# ProPrj___2025-08-19.net
KiCad netlist of a schematic drawn in EasyEDA Pro
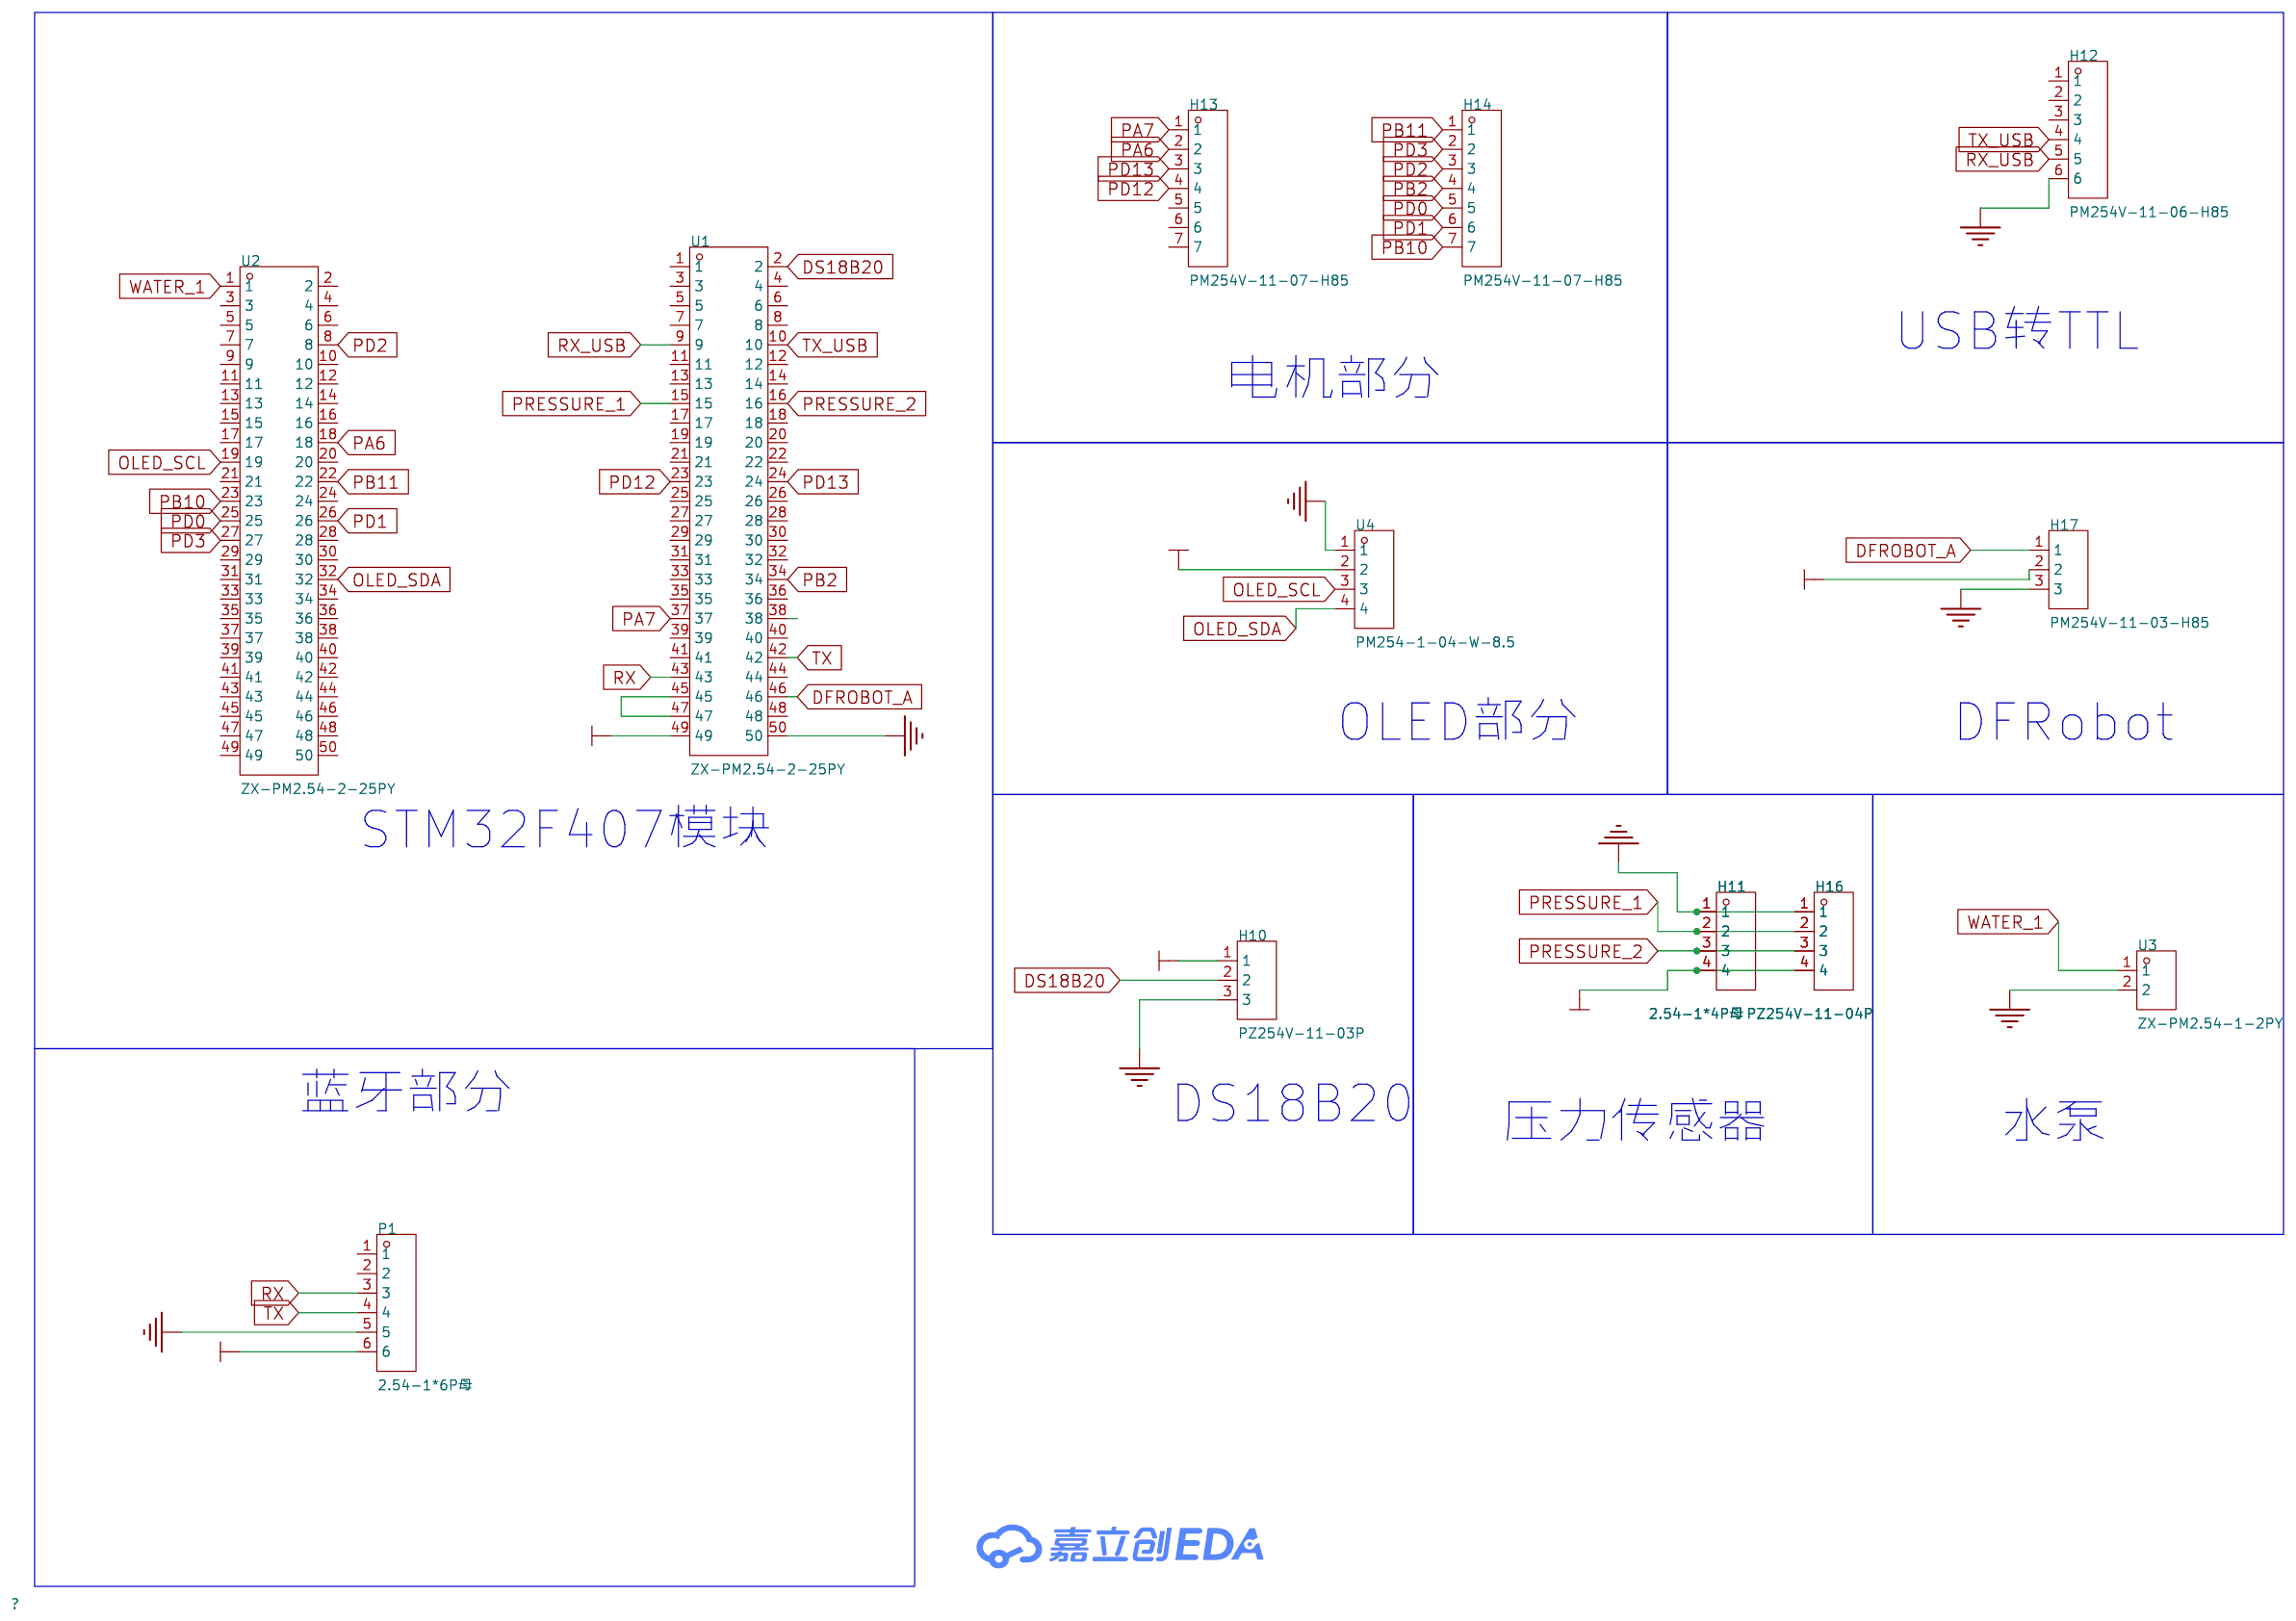
[diagram p0: schematic sheet]

(export (version "E")
  (design (tool "Eeschema 10.0.6"))
  (components
    (comp (ref "H10")
      (value "PZ254V-11-03P")
      (footprint "easyedapro:HDR-TH_3P-P2.54-V-M")
      (fields (field (name "Manufacturer") "XFCN(兴飞)"))
      (libsource (lib "easyedapro") (part "PZ254V-11-03P_C2937625"))
    )
    (comp (ref "H11")
      (value "2.54-1*4P母")
      (footprint "easyedapro:HDR-TH_4P-P2.54-V-F")
      (fields (field (name "Manufacturer") "BOOMELE(博穆精密)"))
      (libsource (lib "easyedapro") (part "2.54-1*4P母"))
    )
    (comp (ref "H12")
      (value "PM254V-11-06-H85")
      (footprint "easyedapro:HDR-TH_6P-P2.54-V-F")
      (fields (field (name "Manufacturer") "XFCN(兴飞)"))
      (libsource (lib "easyedapro") (part "PM254V-11-06-H85"))
    )
    (comp (ref "H13")
      (value "PM254V-11-07-H85")
      (footprint "easyedapro:HDR-TH_7P-P2.54-V-F")
      (fields (field (name "Manufacturer") "XFCN(兴飞)"))
      (libsource (lib "easyedapro") (part "PM254V-11-07-H85"))
    )
    (comp (ref "H14")
      (value "PM254V-11-07-H85")
      (footprint "easyedapro:HDR-TH_7P-P2.54-V-F")
      (fields (field (name "Manufacturer") "XFCN(兴飞)"))
      (libsource (lib "easyedapro") (part "PM254V-11-07-H85"))
    )
    (comp (ref "H16")
      (value "PZ254V-11-04P")
      (footprint "easyedapro:HDR-TH_4P-P2.54-V-M")
      (fields (field (name "Manufacturer") "XFCN(兴飞)"))
      (libsource (lib "easyedapro") (part "PZ254V-11-04P_C2691448"))
    )
    (comp (ref "H17")
      (value "PM254V-11-03-H85")
      (footprint "easyedapro:HDR-TH_3P-P2.54-V-F")
      (description "插孔结构:1x3P;间距:2.54mm;行距:-;安装类型:直插;排数:单排;总孔位数:3P;塑高:-;触头材质:黄铜;触头镀层:-;")
      (fields (field (name "Manufacturer") "XFCN(兴飞)"))
      (libsource (lib "easyedapro") (part "PM254V-11-03-H85"))
    )
    (comp (ref "P1")
      (value "2.54-1*6P母")
      (footprint "easyedapro:HDR-TH_6P-P2.54-V-F")
      (description "插孔结构:1x6P;间距:2.54mm;行距:-;安装类型:直插;排数:单排;总孔位数:6P;塑高:-;触头材质:-;触头镀层:-;")
      (fields (field (name "Manufacturer") "BOOMELE(博穆精密)"))
      (libsource (lib "easyedapro") (part "Header-Female-2.54_1x6"))
    )
    (comp (ref "U1")
      (value "ZX-PM2.54-2-25PY")
      (footprint "easyedapro:HDR-TH_50P-P2.54-V-F-R2-C25-S2.54-1")
      (fields (field (name "Manufacturer") "Megastar(兆星)"))
      (libsource (lib "easyedapro") (part "ZX-PM2.54-2-25PY"))
    )
    (comp (ref "U2")
      (value "ZX-PM2.54-2-25PY")
      (footprint "easyedapro:HDR-TH_50P-P2.54-V-F-R2-C25-S2.54-1")
      (fields (field (name "Manufacturer") "Megastar(兆星)"))
      (libsource (lib "easyedapro") (part "ZX-PM2.54-2-25PY"))
    )
    (comp (ref "U3")
      (value "ZX-PM2.54-1-2PY")
      (footprint "easyedapro:HDR-TH_2P-P2.54-V-F")
      (fields (field (name "Manufacturer") "Megastar(兆星)"))
      (libsource (lib "easyedapro") (part "ZX-PM2.54-1-2PY"))
    )
    (comp (ref "U4")
      (value "PM254-1-04-W-8.5")
      (footprint "easyedapro:HDR-TH_4P-P2.54-H-F-W10.0-N")
      (fields (field (name "Manufacturer") "HCTL(华灿天禄)"))
      (libsource (lib "easyedapro") (part "PM254-1-04-W-8.5"))
    )
  )
  (nets
    (net (code "1") (name "3.3V") (class "Default")
      (node (ref "H10") (pin "1") (pinfunction "1_1") (pintype "unspecified"))
      (node (ref "H11") (pin "4") (pinfunction "4_4") (pintype "unspecified"))
      (node (ref "H16") (pin "4") (pinfunction "4_4") (pintype "unspecified"))
      (node (ref "H17") (pin "2") (pinfunction "2_2") (pintype "unspecified"))
      (node (ref "P1") (pin "6") (pinfunction "6_6") (pintype "unspecified"))
      (node (ref "U1") (pin "49") (pinfunction "49_49") (pintype "unspecified"))
      (node (ref "U4") (pin "2") (pinfunction "2_2") (pintype "unspecified"))
    )
    (net (code "2") (name "DFROBOT_A") (class "Default")
      (node (ref "H17") (pin "1") (pinfunction "1_1") (pintype "unspecified"))
      (node (ref "U1") (pin "46") (pinfunction "46_46") (pintype "unspecified"))
    )
    (net (code "3") (name "DS18B20") (class "Default")
      (node (ref "H10") (pin "2") (pinfunction "2_2") (pintype "unspecified"))
      (node (ref "U1") (pin "2") (pinfunction "2_2") (pintype "unspecified"))
    )
    (net (code "4") (name "GND") (class "Default")
      (node (ref "H10") (pin "3") (pinfunction "3_3") (pintype "unspecified"))
      (node (ref "H11") (pin "1") (pinfunction "1_1") (pintype "unspecified"))
      (node (ref "H12") (pin "6") (pinfunction "6_6") (pintype "unspecified"))
      (node (ref "H16") (pin "1") (pinfunction "1_1") (pintype "unspecified"))
      (node (ref "H17") (pin "3") (pinfunction "3_3") (pintype "unspecified"))
      (node (ref "P1") (pin "5") (pinfunction "5_5") (pintype "unspecified"))
      (node (ref "U1") (pin "50") (pinfunction "50_50") (pintype "unspecified"))
      (node (ref "U3") (pin "2") (pinfunction "2_2") (pintype "unspecified"))
      (node (ref "U4") (pin "1") (pinfunction "1_1") (pintype "unspecified"))
    )
    (net (code "5") (name "Net-(U1-Pad45)") (class "Default")
      (node (ref "U1") (pin "45") (pinfunction "45_45") (pintype "unspecified"))
      (node (ref "U1") (pin "47") (pinfunction "47_47") (pintype "unspecified"))
    )
    (net (code "6") (name "OLED_SCL") (class "Default")
      (node (ref "U2") (pin "19") (pinfunction "19_19") (pintype "unspecified"))
      (node (ref "U4") (pin "3") (pinfunction "3_3") (pintype "unspecified"))
    )
    (net (code "7") (name "OLED_SDA") (class "Default")
      (node (ref "U2") (pin "32") (pinfunction "32_32") (pintype "unspecified"))
      (node (ref "U4") (pin "4") (pinfunction "4_4") (pintype "unspecified"))
    )
    (net (code "8") (name "PA6") (class "Default")
      (node (ref "H13") (pin "2") (pinfunction "2_2") (pintype "unspecified"))
      (node (ref "U2") (pin "18") (pinfunction "18_18") (pintype "unspecified"))
    )
    (net (code "9") (name "PA7") (class "Default")
      (node (ref "H13") (pin "1") (pinfunction "1_1") (pintype "unspecified"))
      (node (ref "U1") (pin "37") (pinfunction "37_37") (pintype "unspecified"))
    )
    (net (code "10") (name "PB2") (class "Default")
      (node (ref "H14") (pin "4") (pinfunction "4_4") (pintype "unspecified"))
      (node (ref "U1") (pin "34") (pinfunction "34_34") (pintype "unspecified"))
    )
    (net (code "11") (name "PB10") (class "Default")
      (node (ref "H14") (pin "7") (pinfunction "7_7") (pintype "unspecified"))
      (node (ref "U2") (pin "23") (pinfunction "23_23") (pintype "unspecified"))
    )
    (net (code "12") (name "PB11") (class "Default")
      (node (ref "H14") (pin "1") (pinfunction "1_1") (pintype "unspecified"))
      (node (ref "U2") (pin "22") (pinfunction "22_22") (pintype "unspecified"))
    )
    (net (code "13") (name "PD0") (class "Default")
      (node (ref "H14") (pin "5") (pinfunction "5_5") (pintype "unspecified"))
      (node (ref "U2") (pin "25") (pinfunction "25_25") (pintype "unspecified"))
    )
    (net (code "14") (name "PD1") (class "Default")
      (node (ref "H14") (pin "6") (pinfunction "6_6") (pintype "unspecified"))
      (node (ref "U2") (pin "26") (pinfunction "26_26") (pintype "unspecified"))
    )
    (net (code "15") (name "PD2") (class "Default")
      (node (ref "H14") (pin "3") (pinfunction "3_3") (pintype "unspecified"))
      (node (ref "U2") (pin "8") (pinfunction "8_8") (pintype "unspecified"))
    )
    (net (code "16") (name "PD3") (class "Default")
      (node (ref "H14") (pin "2") (pinfunction "2_2") (pintype "unspecified"))
      (node (ref "U2") (pin "27") (pinfunction "27_27") (pintype "unspecified"))
    )
    (net (code "17") (name "PD12") (class "Default")
      (node (ref "H13") (pin "4") (pinfunction "4_4") (pintype "unspecified"))
      (node (ref "U1") (pin "23") (pinfunction "23_23") (pintype "unspecified"))
    )
    (net (code "18") (name "PD13") (class "Default")
      (node (ref "H13") (pin "3") (pinfunction "3_3") (pintype "unspecified"))
      (node (ref "U1") (pin "24") (pinfunction "24_24") (pintype "unspecified"))
    )
    (net (code "19") (name "PRESSURE_1") (class "Default")
      (node (ref "H11") (pin "2") (pinfunction "2_2") (pintype "unspecified"))
      (node (ref "H16") (pin "2") (pinfunction "2_2") (pintype "unspecified"))
      (node (ref "U1") (pin "15") (pinfunction "15_15") (pintype "unspecified"))
    )
    (net (code "20") (name "PRESSURE_2") (class "Default")
      (node (ref "H11") (pin "3") (pinfunction "3_3") (pintype "unspecified"))
      (node (ref "H16") (pin "3") (pinfunction "3_3") (pintype "unspecified"))
      (node (ref "U1") (pin "16") (pinfunction "16_16") (pintype "unspecified"))
    )
    (net (code "21") (name "RX") (class "Default")
      (node (ref "P1") (pin "3") (pinfunction "3_3") (pintype "unspecified"))
      (node (ref "U1") (pin "43") (pinfunction "43_43") (pintype "unspecified"))
    )
    (net (code "22") (name "RX_USB") (class "Default")
      (node (ref "H12") (pin "5") (pinfunction "5_5") (pintype "unspecified"))
      (node (ref "U1") (pin "9") (pinfunction "9_9") (pintype "unspecified"))
    )
    (net (code "23") (name "TX") (class "Default")
      (node (ref "P1") (pin "4") (pinfunction "4_4") (pintype "unspecified"))
      (node (ref "U1") (pin "42") (pinfunction "42_42") (pintype "unspecified"))
    )
    (net (code "24") (name "TX_USB") (class "Default")
      (node (ref "H12") (pin "4") (pinfunction "4_4") (pintype "unspecified"))
      (node (ref "U1") (pin "10") (pinfunction "10_10") (pintype "unspecified"))
    )
    (net (code "25") (name "WATER_1") (class "Default")
      (node (ref "U2") (pin "1") (pinfunction "1_1") (pintype "unspecified"))
      (node (ref "U3") (pin "1") (pinfunction "1_1") (pintype "unspecified"))
    )
    (net (code "26") (name "unconnected-(H12-Pad1)") (class "Default")
      (node (ref "H12") (pin "1") (pinfunction "1_1") (pintype "unspecified"))
    )
    (net (code "27") (name "unconnected-(H12-Pad2)") (class "Default")
      (node (ref "H12") (pin "2") (pinfunction "2_2") (pintype "unspecified"))
    )
    (net (code "28") (name "unconnected-(H12-Pad3)") (class "Default")
      (node (ref "H12") (pin "3") (pinfunction "3_3") (pintype "unspecified"))
    )
    (net (code "29") (name "unconnected-(H13-Pad5)") (class "Default")
      (node (ref "H13") (pin "5") (pinfunction "5_5") (pintype "unspecified"))
    )
    (net (code "30") (name "unconnected-(H13-Pad6)") (class "Default")
      (node (ref "H13") (pin "6") (pinfunction "6_6") (pintype "unspecified"))
    )
    (net (code "31") (name "unconnected-(H13-Pad7)") (class "Default")
      (node (ref "H13") (pin "7") (pinfunction "7_7") (pintype "unspecified"))
    )
    (net (code "32") (name "unconnected-(P1-Pad1)") (class "Default")
      (node (ref "P1") (pin "1") (pinfunction "1_1") (pintype "unspecified"))
    )
    (net (code "33") (name "unconnected-(P1-Pad2)") (class "Default")
      (node (ref "P1") (pin "2") (pinfunction "2_2") (pintype "unspecified"))
    )
    (net (code "34") (name "unconnected-(U1-Pad1)") (class "Default")
      (node (ref "U1") (pin "1") (pinfunction "1_1") (pintype "unspecified"))
    )
    (net (code "35") (name "unconnected-(U1-Pad3)") (class "Default")
      (node (ref "U1") (pin "3") (pinfunction "3_3") (pintype "unspecified"))
    )
    (net (code "36") (name "unconnected-(U1-Pad4)") (class "Default")
      (node (ref "U1") (pin "4") (pinfunction "4_4") (pintype "unspecified"))
    )
    (net (code "37") (name "unconnected-(U1-Pad5)") (class "Default")
      (node (ref "U1") (pin "5") (pinfunction "5_5") (pintype "unspecified"))
    )
    (net (code "38") (name "unconnected-(U1-Pad6)") (class "Default")
      (node (ref "U1") (pin "6") (pinfunction "6_6") (pintype "unspecified"))
    )
    (net (code "39") (name "unconnected-(U1-Pad7)") (class "Default")
      (node (ref "U1") (pin "7") (pinfunction "7_7") (pintype "unspecified"))
    )
    (net (code "40") (name "unconnected-(U1-Pad8)") (class "Default")
      (node (ref "U1") (pin "8") (pinfunction "8_8") (pintype "unspecified"))
    )
    (net (code "41") (name "unconnected-(U1-Pad11)") (class "Default")
      (node (ref "U1") (pin "11") (pinfunction "11_11") (pintype "unspecified"))
    )
    (net (code "42") (name "unconnected-(U1-Pad12)") (class "Default")
      (node (ref "U1") (pin "12") (pinfunction "12_12") (pintype "unspecified"))
    )
    (net (code "43") (name "unconnected-(U1-Pad13)") (class "Default")
      (node (ref "U1") (pin "13") (pinfunction "13_13") (pintype "unspecified"))
    )
    (net (code "44") (name "unconnected-(U1-Pad14)") (class "Default")
      (node (ref "U1") (pin "14") (pinfunction "14_14") (pintype "unspecified"))
    )
    (net (code "45") (name "unconnected-(U1-Pad17)") (class "Default")
      (node (ref "U1") (pin "17") (pinfunction "17_17") (pintype "unspecified"))
    )
    (net (code "46") (name "unconnected-(U1-Pad18)") (class "Default")
      (node (ref "U1") (pin "18") (pinfunction "18_18") (pintype "unspecified"))
    )
    (net (code "47") (name "unconnected-(U1-Pad19)") (class "Default")
      (node (ref "U1") (pin "19") (pinfunction "19_19") (pintype "unspecified"))
    )
    (net (code "48") (name "unconnected-(U1-Pad20)") (class "Default")
      (node (ref "U1") (pin "20") (pinfunction "20_20") (pintype "unspecified"))
    )
    (net (code "49") (name "unconnected-(U1-Pad21)") (class "Default")
      (node (ref "U1") (pin "21") (pinfunction "21_21") (pintype "unspecified"))
    )
    (net (code "50") (name "unconnected-(U1-Pad22)") (class "Default")
      (node (ref "U1") (pin "22") (pinfunction "22_22") (pintype "unspecified"))
    )
    (net (code "51") (name "unconnected-(U1-Pad25)") (class "Default")
      (node (ref "U1") (pin "25") (pinfunction "25_25") (pintype "unspecified"))
    )
    (net (code "52") (name "unconnected-(U1-Pad26)") (class "Default")
      (node (ref "U1") (pin "26") (pinfunction "26_26") (pintype "unspecified"))
    )
    (net (code "53") (name "unconnected-(U1-Pad27)") (class "Default")
      (node (ref "U1") (pin "27") (pinfunction "27_27") (pintype "unspecified"))
    )
    (net (code "54") (name "unconnected-(U1-Pad28)") (class "Default")
      (node (ref "U1") (pin "28") (pinfunction "28_28") (pintype "unspecified"))
    )
    (net (code "55") (name "unconnected-(U1-Pad29)") (class "Default")
      (node (ref "U1") (pin "29") (pinfunction "29_29") (pintype "unspecified"))
    )
    (net (code "56") (name "unconnected-(U1-Pad30)") (class "Default")
      (node (ref "U1") (pin "30") (pinfunction "30_30") (pintype "unspecified"))
    )
    (net (code "57") (name "unconnected-(U1-Pad31)") (class "Default")
      (node (ref "U1") (pin "31") (pinfunction "31_31") (pintype "unspecified"))
    )
    (net (code "58") (name "unconnected-(U1-Pad32)") (class "Default")
      (node (ref "U1") (pin "32") (pinfunction "32_32") (pintype "unspecified"))
    )
    (net (code "59") (name "unconnected-(U1-Pad33)") (class "Default")
      (node (ref "U1") (pin "33") (pinfunction "33_33") (pintype "unspecified"))
    )
    (net (code "60") (name "unconnected-(U1-Pad35)") (class "Default")
      (node (ref "U1") (pin "35") (pinfunction "35_35") (pintype "unspecified"))
    )
    (net (code "61") (name "unconnected-(U1-Pad36)") (class "Default")
      (node (ref "U1") (pin "36") (pinfunction "36_36") (pintype "unspecified"))
    )
    (net (code "62") (name "unconnected-(U1-Pad38)") (class "Default")
      (node (ref "U1") (pin "38") (pinfunction "38_38") (pintype "unspecified"))
    )
    (net (code "63") (name "unconnected-(U1-Pad39)") (class "Default")
      (node (ref "U1") (pin "39") (pinfunction "39_39") (pintype "unspecified"))
    )
    (net (code "64") (name "unconnected-(U1-Pad40)") (class "Default")
      (node (ref "U1") (pin "40") (pinfunction "40_40") (pintype "unspecified"))
    )
    (net (code "65") (name "unconnected-(U1-Pad41)") (class "Default")
      (node (ref "U1") (pin "41") (pinfunction "41_41") (pintype "unspecified"))
    )
    (net (code "66") (name "unconnected-(U1-Pad44)") (class "Default")
      (node (ref "U1") (pin "44") (pinfunction "44_44") (pintype "unspecified"))
    )
    (net (code "67") (name "unconnected-(U1-Pad48)") (class "Default")
      (node (ref "U1") (pin "48") (pinfunction "48_48") (pintype "unspecified"))
    )
    (net (code "68") (name "unconnected-(U2-Pad2)") (class "Default")
      (node (ref "U2") (pin "2") (pinfunction "2_2") (pintype "unspecified"))
    )
    (net (code "69") (name "unconnected-(U2-Pad3)") (class "Default")
      (node (ref "U2") (pin "3") (pinfunction "3_3") (pintype "unspecified"))
    )
    (net (code "70") (name "unconnected-(U2-Pad4)") (class "Default")
      (node (ref "U2") (pin "4") (pinfunction "4_4") (pintype "unspecified"))
    )
    (net (code "71") (name "unconnected-(U2-Pad5)") (class "Default")
      (node (ref "U2") (pin "5") (pinfunction "5_5") (pintype "unspecified"))
    )
    (net (code "72") (name "unconnected-(U2-Pad6)") (class "Default")
      (node (ref "U2") (pin "6") (pinfunction "6_6") (pintype "unspecified"))
    )
    (net (code "73") (name "unconnected-(U2-Pad7)") (class "Default")
      (node (ref "U2") (pin "7") (pinfunction "7_7") (pintype "unspecified"))
    )
    (net (code "74") (name "unconnected-(U2-Pad9)") (class "Default")
      (node (ref "U2") (pin "9") (pinfunction "9_9") (pintype "unspecified"))
    )
    (net (code "75") (name "unconnected-(U2-Pad10)") (class "Default")
      (node (ref "U2") (pin "10") (pinfunction "10_10") (pintype "unspecified"))
    )
    (net (code "76") (name "unconnected-(U2-Pad11)") (class "Default")
      (node (ref "U2") (pin "11") (pinfunction "11_11") (pintype "unspecified"))
    )
    (net (code "77") (name "unconnected-(U2-Pad12)") (class "Default")
      (node (ref "U2") (pin "12") (pinfunction "12_12") (pintype "unspecified"))
    )
    (net (code "78") (name "unconnected-(U2-Pad13)") (class "Default")
      (node (ref "U2") (pin "13") (pinfunction "13_13") (pintype "unspecified"))
    )
    (net (code "79") (name "unconnected-(U2-Pad14)") (class "Default")
      (node (ref "U2") (pin "14") (pinfunction "14_14") (pintype "unspecified"))
    )
    (net (code "80") (name "unconnected-(U2-Pad15)") (class "Default")
      (node (ref "U2") (pin "15") (pinfunction "15_15") (pintype "unspecified"))
    )
    (net (code "81") (name "unconnected-(U2-Pad16)") (class "Default")
      (node (ref "U2") (pin "16") (pinfunction "16_16") (pintype "unspecified"))
    )
    (net (code "82") (name "unconnected-(U2-Pad17)") (class "Default")
      (node (ref "U2") (pin "17") (pinfunction "17_17") (pintype "unspecified"))
    )
    (net (code "83") (name "unconnected-(U2-Pad20)") (class "Default")
      (node (ref "U2") (pin "20") (pinfunction "20_20") (pintype "unspecified"))
    )
    (net (code "84") (name "unconnected-(U2-Pad21)") (class "Default")
      (node (ref "U2") (pin "21") (pinfunction "21_21") (pintype "unspecified"))
    )
    (net (code "85") (name "unconnected-(U2-Pad24)") (class "Default")
      (node (ref "U2") (pin "24") (pinfunction "24_24") (pintype "unspecified"))
    )
    (net (code "86") (name "unconnected-(U2-Pad28)") (class "Default")
      (node (ref "U2") (pin "28") (pinfunction "28_28") (pintype "unspecified"))
    )
    (net (code "87") (name "unconnected-(U2-Pad29)") (class "Default")
      (node (ref "U2") (pin "29") (pinfunction "29_29") (pintype "unspecified"))
    )
    (net (code "88") (name "unconnected-(U2-Pad30)") (class "Default")
      (node (ref "U2") (pin "30") (pinfunction "30_30") (pintype "unspecified"))
    )
    (net (code "89") (name "unconnected-(U2-Pad31)") (class "Default")
      (node (ref "U2") (pin "31") (pinfunction "31_31") (pintype "unspecified"))
    )
    (net (code "90") (name "unconnected-(U2-Pad33)") (class "Default")
      (node (ref "U2") (pin "33") (pinfunction "33_33") (pintype "unspecified"))
    )
    (net (code "91") (name "unconnected-(U2-Pad34)") (class "Default")
      (node (ref "U2") (pin "34") (pinfunction "34_34") (pintype "unspecified"))
    )
    (net (code "92") (name "unconnected-(U2-Pad35)") (class "Default")
      (node (ref "U2") (pin "35") (pinfunction "35_35") (pintype "unspecified"))
    )
    (net (code "93") (name "unconnected-(U2-Pad36)") (class "Default")
      (node (ref "U2") (pin "36") (pinfunction "36_36") (pintype "unspecified"))
    )
    (net (code "94") (name "unconnected-(U2-Pad37)") (class "Default")
      (node (ref "U2") (pin "37") (pinfunction "37_37") (pintype "unspecified"))
    )
    (net (code "95") (name "unconnected-(U2-Pad38)") (class "Default")
      (node (ref "U2") (pin "38") (pinfunction "38_38") (pintype "unspecified"))
    )
    (net (code "96") (name "unconnected-(U2-Pad39)") (class "Default")
      (node (ref "U2") (pin "39") (pinfunction "39_39") (pintype "unspecified"))
    )
    (net (code "97") (name "unconnected-(U2-Pad40)") (class "Default")
      (node (ref "U2") (pin "40") (pinfunction "40_40") (pintype "unspecified"))
    )
    (net (code "98") (name "unconnected-(U2-Pad41)") (class "Default")
      (node (ref "U2") (pin "41") (pinfunction "41_41") (pintype "unspecified"))
    )
    (net (code "99") (name "unconnected-(U2-Pad42)") (class "Default")
      (node (ref "U2") (pin "42") (pinfunction "42_42") (pintype "unspecified"))
    )
    (net (code "100") (name "unconnected-(U2-Pad43)") (class "Default")
      (node (ref "U2") (pin "43") (pinfunction "43_43") (pintype "unspecified"))
    )
    (net (code "101") (name "unconnected-(U2-Pad44)") (class "Default")
      (node (ref "U2") (pin "44") (pinfunction "44_44") (pintype "unspecified"))
    )
    (net (code "102") (name "unconnected-(U2-Pad45)") (class "Default")
      (node (ref "U2") (pin "45") (pinfunction "45_45") (pintype "unspecified"))
    )
    (net (code "103") (name "unconnected-(U2-Pad46)") (class "Default")
      (node (ref "U2") (pin "46") (pinfunction "46_46") (pintype "unspecified"))
    )
    (net (code "104") (name "unconnected-(U2-Pad47)") (class "Default")
      (node (ref "U2") (pin "47") (pinfunction "47_47") (pintype "unspecified"))
    )
    (net (code "105") (name "unconnected-(U2-Pad48)") (class "Default")
      (node (ref "U2") (pin "48") (pinfunction "48_48") (pintype "unspecified"))
    )
    (net (code "106") (name "unconnected-(U2-Pad49)") (class "Default")
      (node (ref "U2") (pin "49") (pinfunction "49_49") (pintype "unspecified"))
    )
    (net (code "107") (name "unconnected-(U2-Pad50)") (class "Default")
      (node (ref "U2") (pin "50") (pinfunction "50_50") (pintype "unspecified"))
    )
  )
)
